# Disconnects.net
KiCad netlist of a schematic drawn in Altium Designer
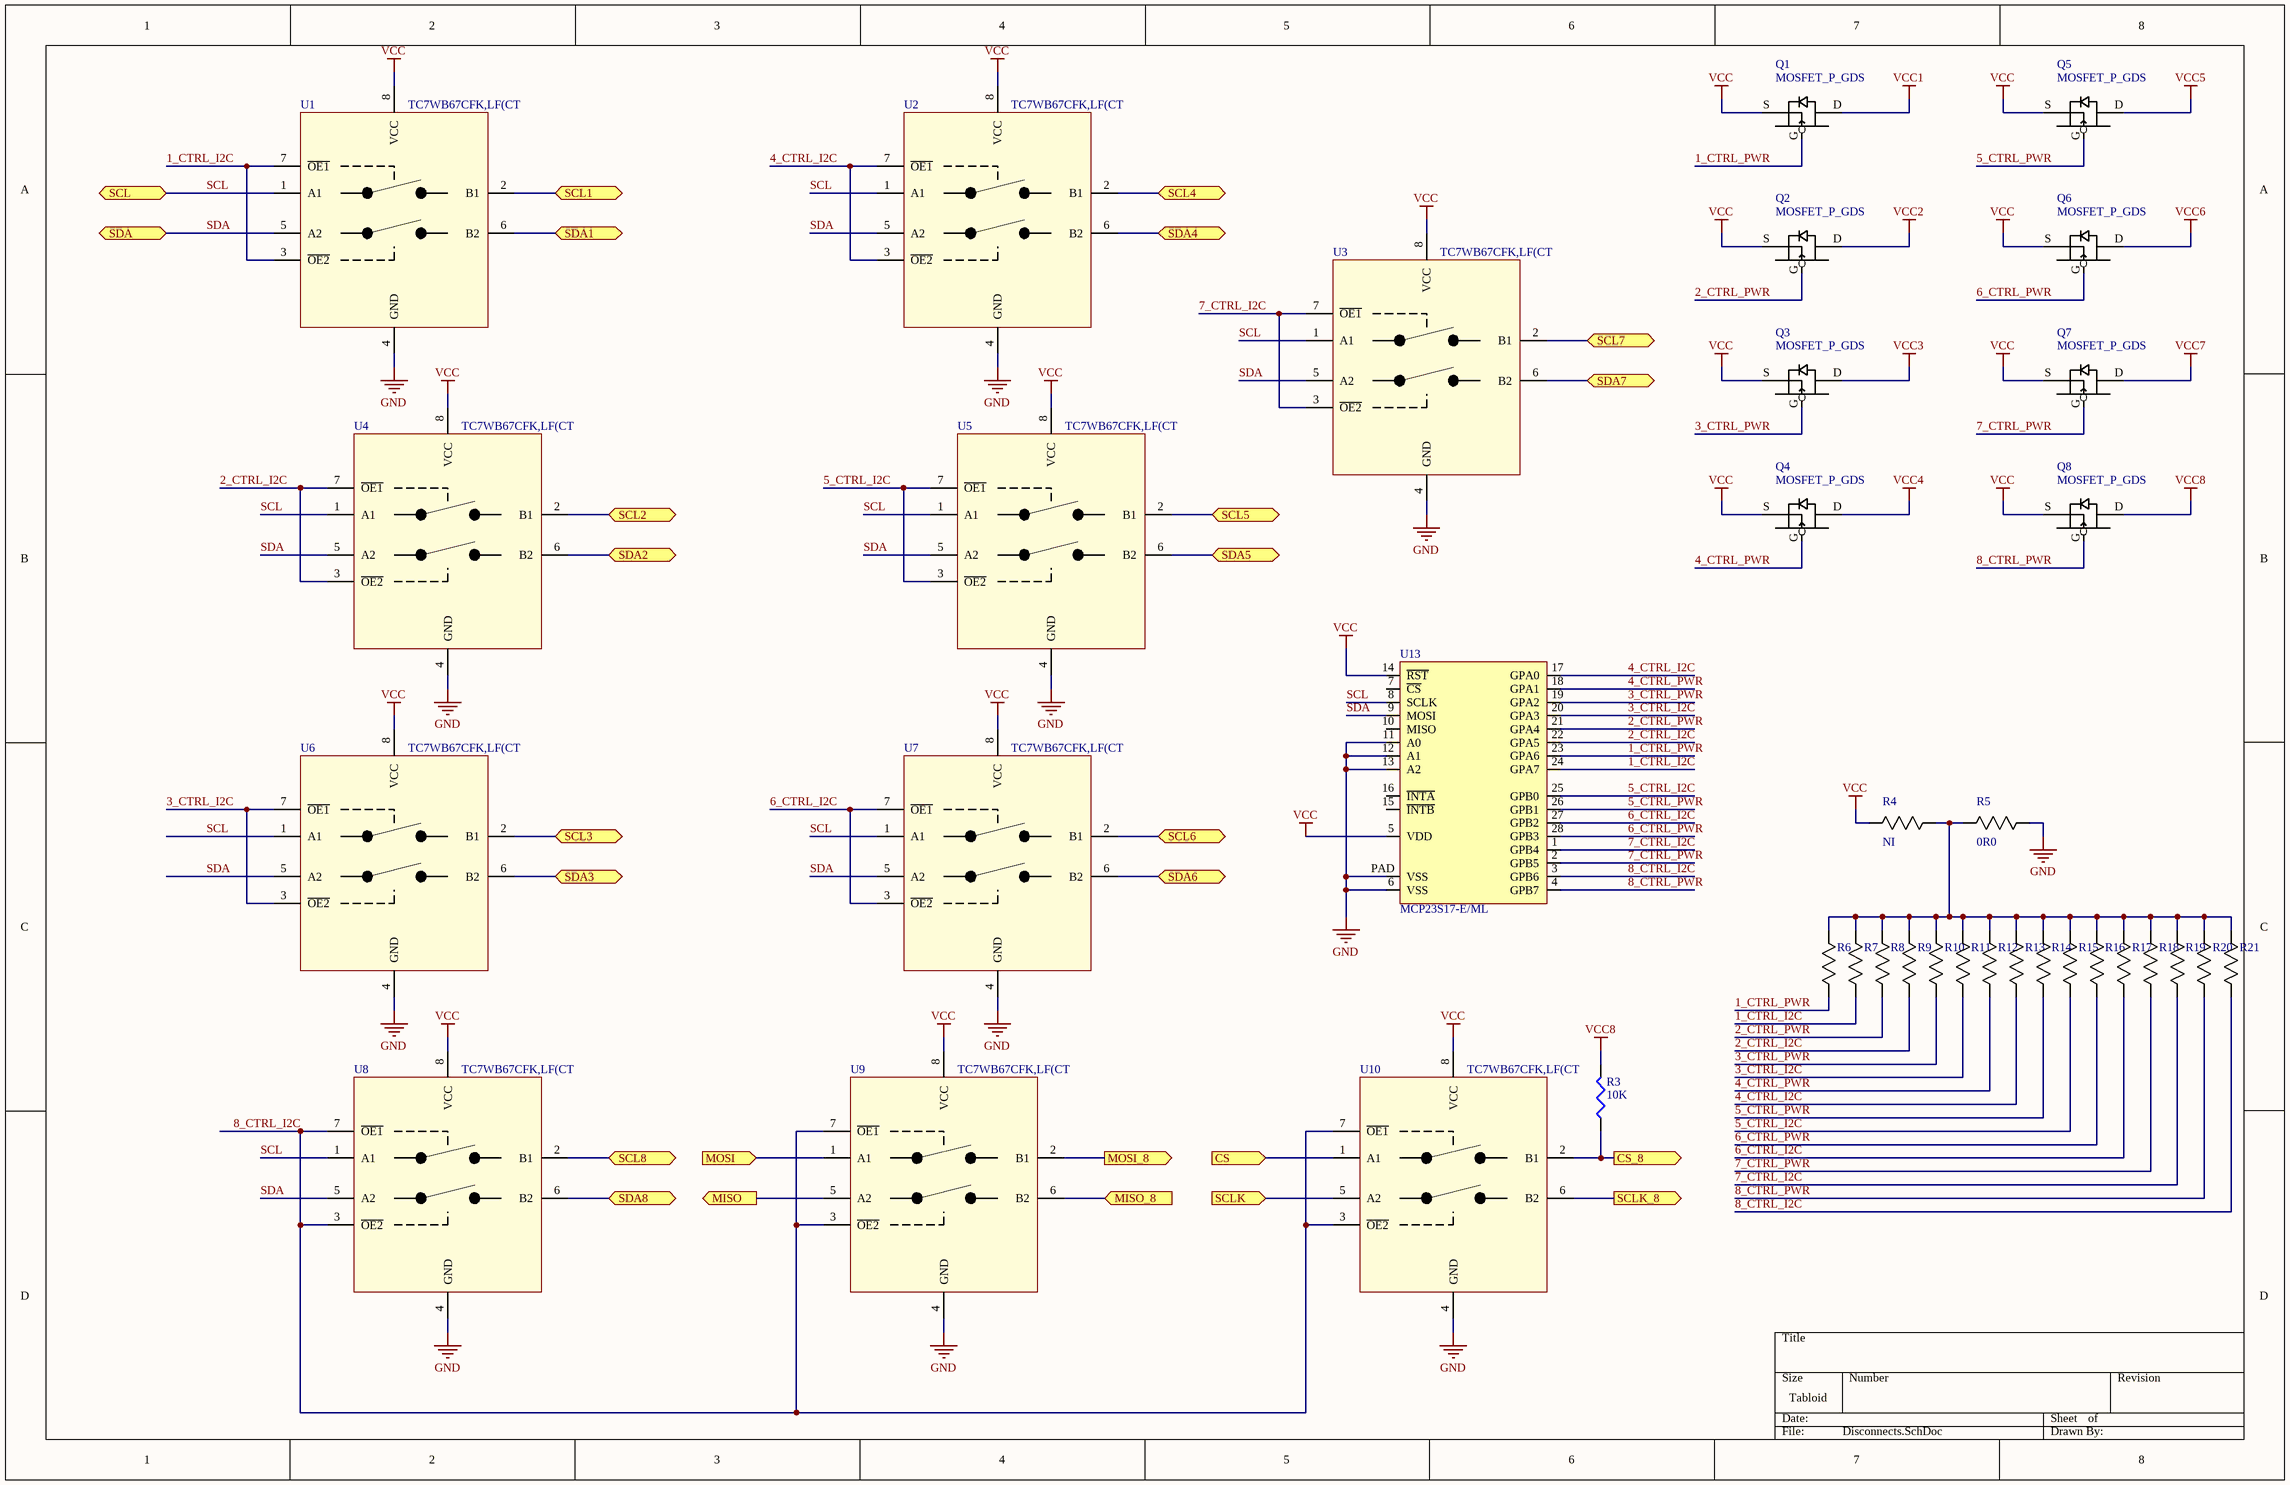
[diagram p0: Disconnects.SchDoc]

(export (version "E")
  (design (tool "Eeschema 10.0.6"))
  (components
    (comp (ref "Q1")
      (value "MOSFET_P_GDS")
      (footprint "SC70_GDS")
      (description "PMOS")
      (fields (field (name "MFG") "OnSemi"))
      (libsource (lib "INTER_2014") (part "MOSFET_P_GDS"))
    )
    (comp (ref "Q2")
      (value "MOSFET_P_GDS")
      (footprint "SC70_GDS")
      (description "PMOS")
      (fields (field (name "MFG") "OnSemi"))
      (libsource (lib "INTER_2014") (part "MOSFET_P_GDS"))
    )
    (comp (ref "Q3")
      (value "MOSFET_P_GDS")
      (footprint "SC70_GDS")
      (description "PMOS")
      (fields (field (name "MFG") "OnSemi"))
      (libsource (lib "INTER_2014") (part "MOSFET_P_GDS"))
    )
    (comp (ref "Q4")
      (value "MOSFET_P_GDS")
      (footprint "SC70_GDS")
      (description "PMOS")
      (fields (field (name "MFG") "OnSemi"))
      (libsource (lib "INTER_2014") (part "MOSFET_P_GDS"))
    )
    (comp (ref "Q5")
      (value "MOSFET_P_GDS")
      (footprint "SC70_GDS")
      (description "PMOS")
      (fields (field (name "MFG") "OnSemi"))
      (libsource (lib "INTER_2014") (part "MOSFET_P_GDS"))
    )
    (comp (ref "Q6")
      (value "MOSFET_P_GDS")
      (footprint "SC70_GDS")
      (description "PMOS")
      (fields (field (name "MFG") "OnSemi"))
      (libsource (lib "INTER_2014") (part "MOSFET_P_GDS"))
    )
    (comp (ref "Q7")
      (value "MOSFET_P_GDS")
      (footprint "SC70_GDS")
      (description "PMOS")
      (fields (field (name "MFG") "OnSemi"))
      (libsource (lib "INTER_2014") (part "MOSFET_P_GDS"))
    )
    (comp (ref "Q8")
      (value "MOSFET_P_GDS")
      (footprint "SC70_GDS")
      (description "PMOS")
      (fields (field (name "MFG") "OnSemi"))
      (libsource (lib "INTER_2014") (part "MOSFET_P_GDS"))
    )
    (comp (ref "R3")
      (value "10K")
      (footprint "6-0805_N")
      (description "Resistor 10K")
      (fields (field (name "Comment") "Res 10K") (field (name "PUBLISHER") "Altium Limited"))
      (libsource (lib "MOvIT-Detect PCB") (part "Res 10K"))
    )
    (comp (ref "R4")
      (value "Resistor")
      (footprint "0603")
      (fields (field (name "MFG") "Bourns") (field (name "NI") "NI"))
      (libsource (lib "INTER_2014") (part "Resistor"))
    )
    (comp (ref "R5")
      (value "0R0")
      (footprint "0603")
      (description "Resistor")
      (fields (field (name "MFG") "KOA"))
      (libsource (lib "INTER_2014") (part "Resistor"))
    )
    (comp (ref "R6")
      (value "Resistor")
      (footprint "0603")
      (fields (field (name "MFG") "Bourns"))
      (libsource (lib "INTER_2014") (part "Resistor"))
    )
    (comp (ref "R7")
      (value "Resistor")
      (footprint "0603")
      (fields (field (name "MFG") "Bourns"))
      (libsource (lib "INTER_2014") (part "Resistor"))
    )
    (comp (ref "R8")
      (value "Resistor")
      (footprint "0603")
      (fields (field (name "MFG") "Bourns"))
      (libsource (lib "INTER_2014") (part "Resistor"))
    )
    (comp (ref "R9")
      (value "Resistor")
      (footprint "0603")
      (fields (field (name "MFG") "Bourns"))
      (libsource (lib "INTER_2014") (part "Resistor"))
    )
    (comp (ref "R10")
      (value "Resistor")
      (footprint "0603")
      (fields (field (name "MFG") "Bourns"))
      (libsource (lib "INTER_2014") (part "Resistor"))
    )
    (comp (ref "R11")
      (value "Resistor")
      (footprint "0603")
      (fields (field (name "MFG") "Bourns"))
      (libsource (lib "INTER_2014") (part "Resistor"))
    )
    (comp (ref "R12")
      (value "Resistor")
      (footprint "0603")
      (fields (field (name "MFG") "Bourns"))
      (libsource (lib "INTER_2014") (part "Resistor"))
    )
    (comp (ref "R13")
      (value "Resistor")
      (footprint "0603")
      (fields (field (name "MFG") "Bourns"))
      (libsource (lib "INTER_2014") (part "Resistor"))
    )
    (comp (ref "R14")
      (value "Resistor")
      (footprint "0603")
      (fields (field (name "MFG") "Bourns"))
      (libsource (lib "INTER_2014") (part "Resistor"))
    )
    (comp (ref "R15")
      (value "Resistor")
      (footprint "0603")
      (fields (field (name "MFG") "Bourns"))
      (libsource (lib "INTER_2014") (part "Resistor"))
    )
    (comp (ref "R16")
      (value "Resistor")
      (footprint "0603")
      (fields (field (name "MFG") "Bourns"))
      (libsource (lib "INTER_2014") (part "Resistor"))
    )
    (comp (ref "R17")
      (value "Resistor")
      (footprint "0603")
      (fields (field (name "MFG") "Bourns"))
      (libsource (lib "INTER_2014") (part "Resistor"))
    )
    (comp (ref "R18")
      (value "Resistor")
      (footprint "0603")
      (fields (field (name "MFG") "Bourns"))
      (libsource (lib "INTER_2014") (part "Resistor"))
    )
    (comp (ref "R19")
      (value "Resistor")
      (footprint "0603")
      (fields (field (name "MFG") "Bourns"))
      (libsource (lib "INTER_2014") (part "Resistor"))
    )
    (comp (ref "R20")
      (value "Resistor")
      (footprint "0603")
      (fields (field (name "MFG") "Bourns"))
      (libsource (lib "INTER_2014") (part "Resistor"))
    )
    (comp (ref "R21")
      (value "Resistor")
      (footprint "0603")
      (fields (field (name "MFG") "Bourns"))
      (libsource (lib "INTER_2014") (part "Resistor"))
    )
    (comp (ref "U1")
      (value "TC7WB67CFK,LF")
      (footprint "PSOP8")
      (description "Dual analog switch")
      (fields (field (name "MFG") "Toshiba") (field (name "MFG_PN") "TC7WB67CFK,LF(CT"))
      (libsource (lib "INTER_2014") (part "TC7WB67CFK,LF"))
    )
    (comp (ref "U2")
      (value "TC7WB67CFK,LF")
      (footprint "PSOP8")
      (description "Dual analog switch")
      (fields (field (name "MFG") "Toshiba") (field (name "MFG_PN") "TC7WB67CFK,LF(CT"))
      (libsource (lib "INTER_2014") (part "TC7WB67CFK,LF"))
    )
    (comp (ref "U3")
      (value "TC7WB67CFK,LF")
      (footprint "PSOP8")
      (description "Dual analog switch")
      (fields (field (name "MFG") "Toshiba") (field (name "MFG_PN") "TC7WB67CFK,LF(CT"))
      (libsource (lib "INTER_2014") (part "TC7WB67CFK,LF"))
    )
    (comp (ref "U4")
      (value "TC7WB67CFK,LF")
      (footprint "PSOP8")
      (description "Dual analog switch")
      (fields (field (name "MFG") "Toshiba") (field (name "MFG_PN") "TC7WB67CFK,LF(CT"))
      (libsource (lib "INTER_2014") (part "TC7WB67CFK,LF"))
    )
    (comp (ref "U5")
      (value "TC7WB67CFK,LF")
      (footprint "PSOP8")
      (description "Dual analog switch")
      (fields (field (name "MFG") "Toshiba") (field (name "MFG_PN") "TC7WB67CFK,LF(CT"))
      (libsource (lib "INTER_2014") (part "TC7WB67CFK,LF"))
    )
    (comp (ref "U6")
      (value "TC7WB67CFK,LF")
      (footprint "PSOP8")
      (description "Dual analog switch")
      (fields (field (name "MFG") "Toshiba") (field (name "MFG_PN") "TC7WB67CFK,LF(CT"))
      (libsource (lib "INTER_2014") (part "TC7WB67CFK,LF"))
    )
    (comp (ref "U7")
      (value "TC7WB67CFK,LF")
      (footprint "PSOP8")
      (description "Dual analog switch")
      (fields (field (name "MFG") "Toshiba") (field (name "MFG_PN") "TC7WB67CFK,LF(CT"))
      (libsource (lib "INTER_2014") (part "TC7WB67CFK,LF"))
    )
    (comp (ref "U8")
      (value "TC7WB67CFK,LF")
      (footprint "PSOP8")
      (description "Dual analog switch")
      (fields (field (name "MFG") "Toshiba") (field (name "MFG_PN") "TC7WB67CFK,LF(CT"))
      (libsource (lib "INTER_2014") (part "TC7WB67CFK,LF"))
    )
    (comp (ref "U9")
      (value "TC7WB67CFK,LF")
      (footprint "PSOP8")
      (description "Dual analog switch")
      (fields (field (name "MFG") "Toshiba") (field (name "MFG_PN") "TC7WB67CFK,LF(CT"))
      (libsource (lib "INTER_2014") (part "TC7WB67CFK,LF"))
    )
    (comp (ref "U10")
      (value "TC7WB67CFK,LF")
      (footprint "PSOP8")
      (description "Dual analog switch")
      (fields (field (name "MFG") "Toshiba") (field (name "MFG_PN") "TC7WB67CFK,LF(CT"))
      (libsource (lib "INTER_2014") (part "TC7WB67CFK,LF"))
    )
    (comp (ref "U13")
      (value "MCP23S17-E/ML")
      (footprint "QFN28-S")
      (description "16-Bit SPI I/O Expander")
      (fields (field (name "MFG") "Microchip"))
      (libsource (lib "INTER_2014") (part "MCP23S17-E/ML"))
    )
  )
  (nets
    (net (code "1") (name "/1_CTRL_I2C") (class "Default")
      (node (ref "R7") (pin "2") (pintype "passive"))
      (node (ref "U1") (pin "3") (pinfunction "~{OE2}_3") (pintype "passive"))
      (node (ref "U1") (pin "7") (pinfunction "~{OE1}_7") (pintype "passive"))
      (node (ref "U13") (pin "24") (pinfunction "GPA7_24") (pintype "passive"))
    )
    (net (code "2") (name "/1_CTRL_PWR") (class "Default")
      (node (ref "Q1") (pin "G") (pintype "passive"))
      (node (ref "R6") (pin "2") (pintype "passive"))
      (node (ref "U13") (pin "23") (pinfunction "GPA6_23") (pintype "passive"))
    )
    (net (code "3") (name "/2_CTRL_I2C") (class "Default")
      (node (ref "R9") (pin "2") (pintype "passive"))
      (node (ref "U13") (pin "22") (pinfunction "GPA5_22") (pintype "passive"))
      (node (ref "U4") (pin "3") (pinfunction "~{OE2}_3") (pintype "passive"))
      (node (ref "U4") (pin "7") (pinfunction "~{OE1}_7") (pintype "passive"))
    )
    (net (code "4") (name "/2_CTRL_PWR") (class "Default")
      (node (ref "Q2") (pin "G") (pintype "passive"))
      (node (ref "R8") (pin "2") (pintype "passive"))
      (node (ref "U13") (pin "21") (pinfunction "GPA4_21") (pintype "passive"))
    )
    (net (code "5") (name "/3_CTRL_I2C") (class "Default")
      (node (ref "R11") (pin "2") (pintype "passive"))
      (node (ref "U13") (pin "20") (pinfunction "GPA3_20") (pintype "passive"))
      (node (ref "U6") (pin "3") (pinfunction "~{OE2}_3") (pintype "passive"))
      (node (ref "U6") (pin "7") (pinfunction "~{OE1}_7") (pintype "passive"))
    )
    (net (code "6") (name "/3_CTRL_PWR") (class "Default")
      (node (ref "Q3") (pin "G") (pintype "passive"))
      (node (ref "R10") (pin "2") (pintype "passive"))
      (node (ref "U13") (pin "19") (pinfunction "GPA2_19") (pintype "passive"))
    )
    (net (code "7") (name "/4_CTRL_I2C") (class "Default")
      (node (ref "R13") (pin "2") (pintype "passive"))
      (node (ref "U13") (pin "17") (pinfunction "GPA0_17") (pintype "passive"))
      (node (ref "U2") (pin "3") (pinfunction "~{OE2}_3") (pintype "passive"))
      (node (ref "U2") (pin "7") (pinfunction "~{OE1}_7") (pintype "passive"))
    )
    (net (code "8") (name "/4_CTRL_PWR") (class "Default")
      (node (ref "Q4") (pin "G") (pintype "passive"))
      (node (ref "R12") (pin "2") (pintype "passive"))
      (node (ref "U13") (pin "18") (pinfunction "GPA1_18") (pintype "passive"))
    )
    (net (code "9") (name "/5_CTRL_I2C") (class "Default")
      (node (ref "R15") (pin "2") (pintype "passive"))
      (node (ref "U13") (pin "25") (pinfunction "GPB0_25") (pintype "passive"))
      (node (ref "U5") (pin "3") (pinfunction "~{OE2}_3") (pintype "passive"))
      (node (ref "U5") (pin "7") (pinfunction "~{OE1}_7") (pintype "passive"))
    )
    (net (code "10") (name "/5_CTRL_PWR") (class "Default")
      (node (ref "Q5") (pin "G") (pintype "passive"))
      (node (ref "R14") (pin "2") (pintype "passive"))
      (node (ref "U13") (pin "26") (pinfunction "GPB1_26") (pintype "passive"))
    )
    (net (code "11") (name "/6_CTRL_I2C") (class "Default")
      (node (ref "R17") (pin "2") (pintype "passive"))
      (node (ref "U13") (pin "27") (pinfunction "GPB2_27") (pintype "passive"))
      (node (ref "U7") (pin "3") (pinfunction "~{OE2}_3") (pintype "passive"))
      (node (ref "U7") (pin "7") (pinfunction "~{OE1}_7") (pintype "passive"))
    )
    (net (code "12") (name "/6_CTRL_PWR") (class "Default")
      (node (ref "Q6") (pin "G") (pintype "passive"))
      (node (ref "R16") (pin "2") (pintype "passive"))
      (node (ref "U13") (pin "28") (pinfunction "GPB3_28") (pintype "passive"))
    )
    (net (code "13") (name "/7_CTRL_I2C") (class "Default")
      (node (ref "R19") (pin "2") (pintype "passive"))
      (node (ref "U13") (pin "1") (pinfunction "GPB4_1") (pintype "passive"))
      (node (ref "U3") (pin "3") (pinfunction "~{OE2}_3") (pintype "passive"))
      (node (ref "U3") (pin "7") (pinfunction "~{OE1}_7") (pintype "passive"))
    )
    (net (code "14") (name "/7_CTRL_PWR") (class "Default")
      (node (ref "Q7") (pin "G") (pintype "passive"))
      (node (ref "R18") (pin "2") (pintype "passive"))
      (node (ref "U13") (pin "2") (pinfunction "GPB5_2") (pintype "passive"))
    )
    (net (code "15") (name "/8_CTRL_I2C") (class "Default")
      (node (ref "R21") (pin "2") (pintype "passive"))
      (node (ref "U10") (pin "3") (pinfunction "~{OE2}_3") (pintype "passive"))
      (node (ref "U10") (pin "7") (pinfunction "~{OE1}_7") (pintype "passive"))
      (node (ref "U13") (pin "3") (pinfunction "GPB6_3") (pintype "passive"))
      (node (ref "U8") (pin "3") (pinfunction "~{OE2}_3") (pintype "passive"))
      (node (ref "U8") (pin "7") (pinfunction "~{OE1}_7") (pintype "passive"))
      (node (ref "U9") (pin "3") (pinfunction "~{OE2}_3") (pintype "passive"))
      (node (ref "U9") (pin "7") (pinfunction "~{OE1}_7") (pintype "passive"))
    )
    (net (code "16") (name "/8_CTRL_PWR") (class "Default")
      (node (ref "Q8") (pin "G") (pintype "passive"))
      (node (ref "R20") (pin "2") (pintype "passive"))
      (node (ref "U13") (pin "4") (pinfunction "GPB7_4") (pintype "passive"))
    )
    (net (code "17") (name "/CS") (class "Default")
      (node (ref "U10") (pin "1") (pinfunction "A1_1") (pintype "passive"))
    )
    (net (code "18") (name "/CS_8") (class "Default")
      (node (ref "R3") (pin "1") (pinfunction "1_1") (pintype "passive"))
      (node (ref "U10") (pin "2") (pinfunction "B1_2") (pintype "passive"))
    )
    (net (code "19") (name "/MISO") (class "Default")
      (node (ref "U9") (pin "5") (pinfunction "A2_5") (pintype "passive"))
    )
    (net (code "20") (name "/MISO_8") (class "Default")
      (node (ref "U9") (pin "6") (pinfunction "B2_6") (pintype "passive"))
    )
    (net (code "21") (name "/MOSI") (class "Default")
      (node (ref "U9") (pin "1") (pinfunction "A1_1") (pintype "passive"))
    )
    (net (code "22") (name "/MOSI_8") (class "Default")
      (node (ref "U9") (pin "2") (pinfunction "B1_2") (pintype "passive"))
    )
    (net (code "23") (name "/SCL") (class "Default")
      (node (ref "U1") (pin "1") (pinfunction "A1_1") (pintype "passive"))
      (node (ref "U13") (pin "8") (pinfunction "SCLK_8") (pintype "passive"))
      (node (ref "U2") (pin "1") (pinfunction "A1_1") (pintype "passive"))
      (node (ref "U3") (pin "1") (pinfunction "A1_1") (pintype "passive"))
      (node (ref "U4") (pin "1") (pinfunction "A1_1") (pintype "passive"))
      (node (ref "U5") (pin "1") (pinfunction "A1_1") (pintype "passive"))
      (node (ref "U6") (pin "1") (pinfunction "A1_1") (pintype "passive"))
      (node (ref "U7") (pin "1") (pinfunction "A1_1") (pintype "passive"))
      (node (ref "U8") (pin "1") (pinfunction "A1_1") (pintype "passive"))
    )
    (net (code "24") (name "/SCL1") (class "Default")
      (node (ref "U1") (pin "2") (pinfunction "B1_2") (pintype "passive"))
    )
    (net (code "25") (name "/SCL2") (class "Default")
      (node (ref "U4") (pin "2") (pinfunction "B1_2") (pintype "passive"))
    )
    (net (code "26") (name "/SCL3") (class "Default")
      (node (ref "U6") (pin "2") (pinfunction "B1_2") (pintype "passive"))
    )
    (net (code "27") (name "/SCL4") (class "Default")
      (node (ref "U2") (pin "2") (pinfunction "B1_2") (pintype "passive"))
    )
    (net (code "28") (name "/SCL5") (class "Default")
      (node (ref "U5") (pin "2") (pinfunction "B1_2") (pintype "passive"))
    )
    (net (code "29") (name "/SCL6") (class "Default")
      (node (ref "U7") (pin "2") (pinfunction "B1_2") (pintype "passive"))
    )
    (net (code "30") (name "/SCL7") (class "Default")
      (node (ref "U3") (pin "2") (pinfunction "B1_2") (pintype "passive"))
    )
    (net (code "31") (name "/SCL8") (class "Default")
      (node (ref "U8") (pin "2") (pinfunction "B1_2") (pintype "passive"))
    )
    (net (code "32") (name "/SCLK") (class "Default")
      (node (ref "U10") (pin "5") (pinfunction "A2_5") (pintype "passive"))
    )
    (net (code "33") (name "/SCLK_8") (class "Default")
      (node (ref "U10") (pin "6") (pinfunction "B2_6") (pintype "passive"))
    )
    (net (code "34") (name "/SDA") (class "Default")
      (node (ref "U1") (pin "5") (pinfunction "A2_5") (pintype "passive"))
      (node (ref "U13") (pin "9") (pinfunction "MOSI_9") (pintype "passive"))
      (node (ref "U2") (pin "5") (pinfunction "A2_5") (pintype "passive"))
      (node (ref "U3") (pin "5") (pinfunction "A2_5") (pintype "passive"))
      (node (ref "U4") (pin "5") (pinfunction "A2_5") (pintype "passive"))
      (node (ref "U5") (pin "5") (pinfunction "A2_5") (pintype "passive"))
      (node (ref "U6") (pin "5") (pinfunction "A2_5") (pintype "passive"))
      (node (ref "U7") (pin "5") (pinfunction "A2_5") (pintype "passive"))
      (node (ref "U8") (pin "5") (pinfunction "A2_5") (pintype "passive"))
    )
    (net (code "35") (name "/SDA1") (class "Default")
      (node (ref "U1") (pin "6") (pinfunction "B2_6") (pintype "passive"))
    )
    (net (code "36") (name "/SDA2") (class "Default")
      (node (ref "U4") (pin "6") (pinfunction "B2_6") (pintype "passive"))
    )
    (net (code "37") (name "/SDA3") (class "Default")
      (node (ref "U6") (pin "6") (pinfunction "B2_6") (pintype "passive"))
    )
    (net (code "38") (name "/SDA4") (class "Default")
      (node (ref "U2") (pin "6") (pinfunction "B2_6") (pintype "passive"))
    )
    (net (code "39") (name "/SDA5") (class "Default")
      (node (ref "U5") (pin "6") (pinfunction "B2_6") (pintype "passive"))
    )
    (net (code "40") (name "/SDA6") (class "Default")
      (node (ref "U7") (pin "6") (pinfunction "B2_6") (pintype "passive"))
    )
    (net (code "41") (name "/SDA7") (class "Default")
      (node (ref "U3") (pin "6") (pinfunction "B2_6") (pintype "passive"))
    )
    (net (code "42") (name "/SDA8") (class "Default")
      (node (ref "U8") (pin "6") (pinfunction "B2_6") (pintype "passive"))
    )
    (net (code "43") (name "GND") (class "Default")
      (node (ref "R5") (pin "2") (pintype "passive"))
      (node (ref "U1") (pin "4") (pinfunction "GND_4") (pintype "passive"))
      (node (ref "U10") (pin "4") (pinfunction "GND_4") (pintype "passive"))
      (node (ref "U13") (pin "11") (pinfunction "A0_11") (pintype "passive"))
      (node (ref "U13") (pin "12") (pinfunction "A1_12") (pintype "passive"))
      (node (ref "U13") (pin "13") (pinfunction "A2_13") (pintype "passive"))
      (node (ref "U13") (pin "6") (pinfunction "VSS_6") (pintype "passive"))
      (node (ref "U13") (pin "PAD") (pinfunction "VSS_PAD") (pintype "passive"))
      (node (ref "U2") (pin "4") (pinfunction "GND_4") (pintype "passive"))
      (node (ref "U3") (pin "4") (pinfunction "GND_4") (pintype "passive"))
      (node (ref "U4") (pin "4") (pinfunction "GND_4") (pintype "passive"))
      (node (ref "U5") (pin "4") (pinfunction "GND_4") (pintype "passive"))
      (node (ref "U6") (pin "4") (pinfunction "GND_4") (pintype "passive"))
      (node (ref "U7") (pin "4") (pinfunction "GND_4") (pintype "passive"))
      (node (ref "U8") (pin "4") (pinfunction "GND_4") (pintype "passive"))
      (node (ref "U9") (pin "4") (pinfunction "GND_4") (pintype "passive"))
    )
    (net (code "44") (name "Net-(R10-Pad1)") (class "Default")
      (node (ref "R10") (pin "1") (pintype "passive"))
      (node (ref "R11") (pin "1") (pintype "passive"))
      (node (ref "R12") (pin "1") (pintype "passive"))
      (node (ref "R13") (pin "1") (pintype "passive"))
      (node (ref "R14") (pin "1") (pintype "passive"))
      (node (ref "R15") (pin "1") (pintype "passive"))
      (node (ref "R16") (pin "1") (pintype "passive"))
      (node (ref "R17") (pin "1") (pintype "passive"))
      (node (ref "R18") (pin "1") (pintype "passive"))
      (node (ref "R19") (pin "1") (pintype "passive"))
      (node (ref "R20") (pin "1") (pintype "passive"))
      (node (ref "R21") (pin "1") (pintype "passive"))
      (node (ref "R4") (pin "2") (pintype "passive"))
      (node (ref "R5") (pin "1") (pintype "passive"))
      (node (ref "R6") (pin "1") (pintype "passive"))
      (node (ref "R7") (pin "1") (pintype "passive"))
      (node (ref "R8") (pin "1") (pintype "passive"))
      (node (ref "R9") (pin "1") (pintype "passive"))
    )
    (net (code "45") (name "VCC") (class "Default")
      (node (ref "Q1") (pin "S") (pintype "passive"))
      (node (ref "Q2") (pin "S") (pintype "passive"))
      (node (ref "Q3") (pin "S") (pintype "passive"))
      (node (ref "Q4") (pin "S") (pintype "passive"))
      (node (ref "Q5") (pin "S") (pintype "passive"))
      (node (ref "Q6") (pin "S") (pintype "passive"))
      (node (ref "Q7") (pin "S") (pintype "passive"))
      (node (ref "Q8") (pin "S") (pintype "passive"))
      (node (ref "R4") (pin "1") (pintype "passive"))
      (node (ref "U1") (pin "8") (pinfunction "VCC_8") (pintype "passive"))
      (node (ref "U10") (pin "8") (pinfunction "VCC_8") (pintype "passive"))
      (node (ref "U13") (pin "14") (pinfunction "~{RST}_14") (pintype "passive"))
      (node (ref "U13") (pin "5") (pinfunction "VDD_5") (pintype "passive"))
      (node (ref "U2") (pin "8") (pinfunction "VCC_8") (pintype "passive"))
      (node (ref "U3") (pin "8") (pinfunction "VCC_8") (pintype "passive"))
      (node (ref "U4") (pin "8") (pinfunction "VCC_8") (pintype "passive"))
      (node (ref "U5") (pin "8") (pinfunction "VCC_8") (pintype "passive"))
      (node (ref "U6") (pin "8") (pinfunction "VCC_8") (pintype "passive"))
      (node (ref "U7") (pin "8") (pinfunction "VCC_8") (pintype "passive"))
      (node (ref "U8") (pin "8") (pinfunction "VCC_8") (pintype "passive"))
      (node (ref "U9") (pin "8") (pinfunction "VCC_8") (pintype "passive"))
    )
    (net (code "46") (name "VCC1") (class "Default") (node (ref "Q1") (pin "D") (pintype "passive")))
    (net (code "47") (name "VCC2") (class "Default") (node (ref "Q2") (pin "D") (pintype "passive")))
    (net (code "48") (name "VCC3") (class "Default") (node (ref "Q3") (pin "D") (pintype "passive")))
    (net (code "49") (name "VCC4") (class "Default") (node (ref "Q4") (pin "D") (pintype "passive")))
    (net (code "50") (name "VCC5") (class "Default") (node (ref "Q5") (pin "D") (pintype "passive")))
    (net (code "51") (name "VCC6") (class "Default") (node (ref "Q6") (pin "D") (pintype "passive")))
    (net (code "52") (name "VCC7") (class "Default") (node (ref "Q7") (pin "D") (pintype "passive")))
    (net (code "53") (name "VCC8") (class "Default")
      (node (ref "Q8") (pin "D") (pintype "passive"))
      (node (ref "R3") (pin "2") (pinfunction "2_2") (pintype "passive"))
    )
    (net (code "54") (name "unconnected-(U13-MISO-Pad10)") (class "Default")
      (node (ref "U13") (pin "10") (pinfunction "MISO_10") (pintype "passive"))
    )
    (net (code "55") (name "unconnected-(U13-~{CS}-Pad7)") (class "Default")
      (node (ref "U13") (pin "7") (pinfunction "~{CS}_7") (pintype "passive"))
    )
    (net (code "56") (name "unconnected-(U13-~{INTA}-Pad16)") (class "Default")
      (node (ref "U13") (pin "16") (pinfunction "~{INTA}_16") (pintype "passive"))
    )
    (net (code "57") (name "unconnected-(U13-~{INTB}-Pad15)") (class "Default")
      (node (ref "U13") (pin "15") (pinfunction "~{INTB}_15") (pintype "passive"))
    )
  )
)
